# Ladybug.net
KiCad netlist of a schematic drawn in EAGLE
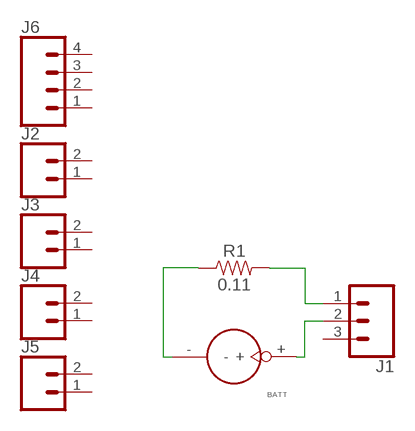
[diagram p0: schematic, sheet 1]

(export (version "E")
  (design (tool "Eeschema 10.0.6"))
  (components
    (comp (ref "BATT")
      (value "BATTERY_1236_C")
      (footprint "eagle-import:BATTERY_1236_C")
      (libsource (lib "eagle-import") (part "BATTERY_1236_C"))
    )
    (comp (ref "J1")
      (value "CONN_03LOCK")
      (footprint "eagle-import:1X03_LOCK")
      (libsource (lib "eagle-import") (part "CONN_03LOCK"))
    )
    (comp (ref "J2")
      (value "CONN_02")
      (footprint "eagle-import:1X02")
      (libsource (lib "eagle-import") (part "CONN_02"))
    )
    (comp (ref "J3")
      (value "CONN_02")
      (footprint "eagle-import:1X02")
      (libsource (lib "eagle-import") (part "CONN_02"))
    )
    (comp (ref "J4")
      (value "CONN_02")
      (footprint "eagle-import:1X02")
      (libsource (lib "eagle-import") (part "CONN_02"))
    )
    (comp (ref "J5")
      (value "CONN_02")
      (footprint "eagle-import:1X02")
      (libsource (lib "eagle-import") (part "CONN_02"))
    )
    (comp (ref "J6")
      (value "CONN_04")
      (footprint "eagle-import:1X04")
      (libsource (lib "eagle-import") (part "CONN_04"))
    )
    (comp (ref "R1")
      (value "0.11")
      (footprint "eagle-import:2010")
      (libsource (lib "eagle-import") (part "0.11OHM-2010-1/2W-1%"))
    )
  )
  (nets
    (net (code "1") (name "Net-(BATT-Pad+)") (class "Default")
      (node (ref "BATT") (pin "+") (pinfunction "+_+") (pintype "bidirectional"))
      (node (ref "J1") (pin "2") (pinfunction "2_2") (pintype "passive"))
    )
    (net (code "2") (name "Net-(BATT-Pad-)") (class "Default")
      (node (ref "BATT") (pin "-") (pinfunction "-_-") (pintype "bidirectional"))
      (node (ref "R1") (pin "1") (pinfunction "1_1") (pintype "passive"))
    )
    (net (code "3") (name "Net-(J1-Pad1)") (class "Default")
      (node (ref "J1") (pin "1") (pinfunction "1_1") (pintype "passive"))
      (node (ref "R1") (pin "2") (pinfunction "2_2") (pintype "passive"))
    )
    (net (code "4") (name "unconnected-(J1-Pad3)") (class "Default")
      (node (ref "J1") (pin "3") (pinfunction "3_3") (pintype "passive"))
    )
    (net (code "5") (name "unconnected-(J2-Pad1)") (class "Default")
      (node (ref "J2") (pin "1") (pinfunction "1_1") (pintype "passive"))
    )
    (net (code "6") (name "unconnected-(J2-Pad2)") (class "Default")
      (node (ref "J2") (pin "2") (pinfunction "2_2") (pintype "passive"))
    )
    (net (code "7") (name "unconnected-(J3-Pad1)") (class "Default")
      (node (ref "J3") (pin "1") (pinfunction "1_1") (pintype "passive"))
    )
    (net (code "8") (name "unconnected-(J3-Pad2)") (class "Default")
      (node (ref "J3") (pin "2") (pinfunction "2_2") (pintype "passive"))
    )
    (net (code "9") (name "unconnected-(J4-Pad1)") (class "Default")
      (node (ref "J4") (pin "1") (pinfunction "1_1") (pintype "passive"))
    )
    (net (code "10") (name "unconnected-(J4-Pad2)") (class "Default")
      (node (ref "J4") (pin "2") (pinfunction "2_2") (pintype "passive"))
    )
    (net (code "11") (name "unconnected-(J5-Pad1)") (class "Default")
      (node (ref "J5") (pin "1") (pinfunction "1_1") (pintype "passive"))
    )
    (net (code "12") (name "unconnected-(J5-Pad2)") (class "Default")
      (node (ref "J5") (pin "2") (pinfunction "2_2") (pintype "passive"))
    )
    (net (code "13") (name "unconnected-(J6-Pad1)") (class "Default")
      (node (ref "J6") (pin "1") (pinfunction "1_1") (pintype "passive"))
    )
    (net (code "14") (name "unconnected-(J6-Pad2)") (class "Default")
      (node (ref "J6") (pin "2") (pinfunction "2_2") (pintype "passive"))
    )
    (net (code "15") (name "unconnected-(J6-Pad3)") (class "Default")
      (node (ref "J6") (pin "3") (pinfunction "3_3") (pintype "passive"))
    )
    (net (code "16") (name "unconnected-(J6-Pad4)") (class "Default")
      (node (ref "J6") (pin "4") (pinfunction "4_4") (pintype "passive"))
    )
  )
)
